# Transformer.net
KiCad netlist of a schematic drawn in Altium Designer
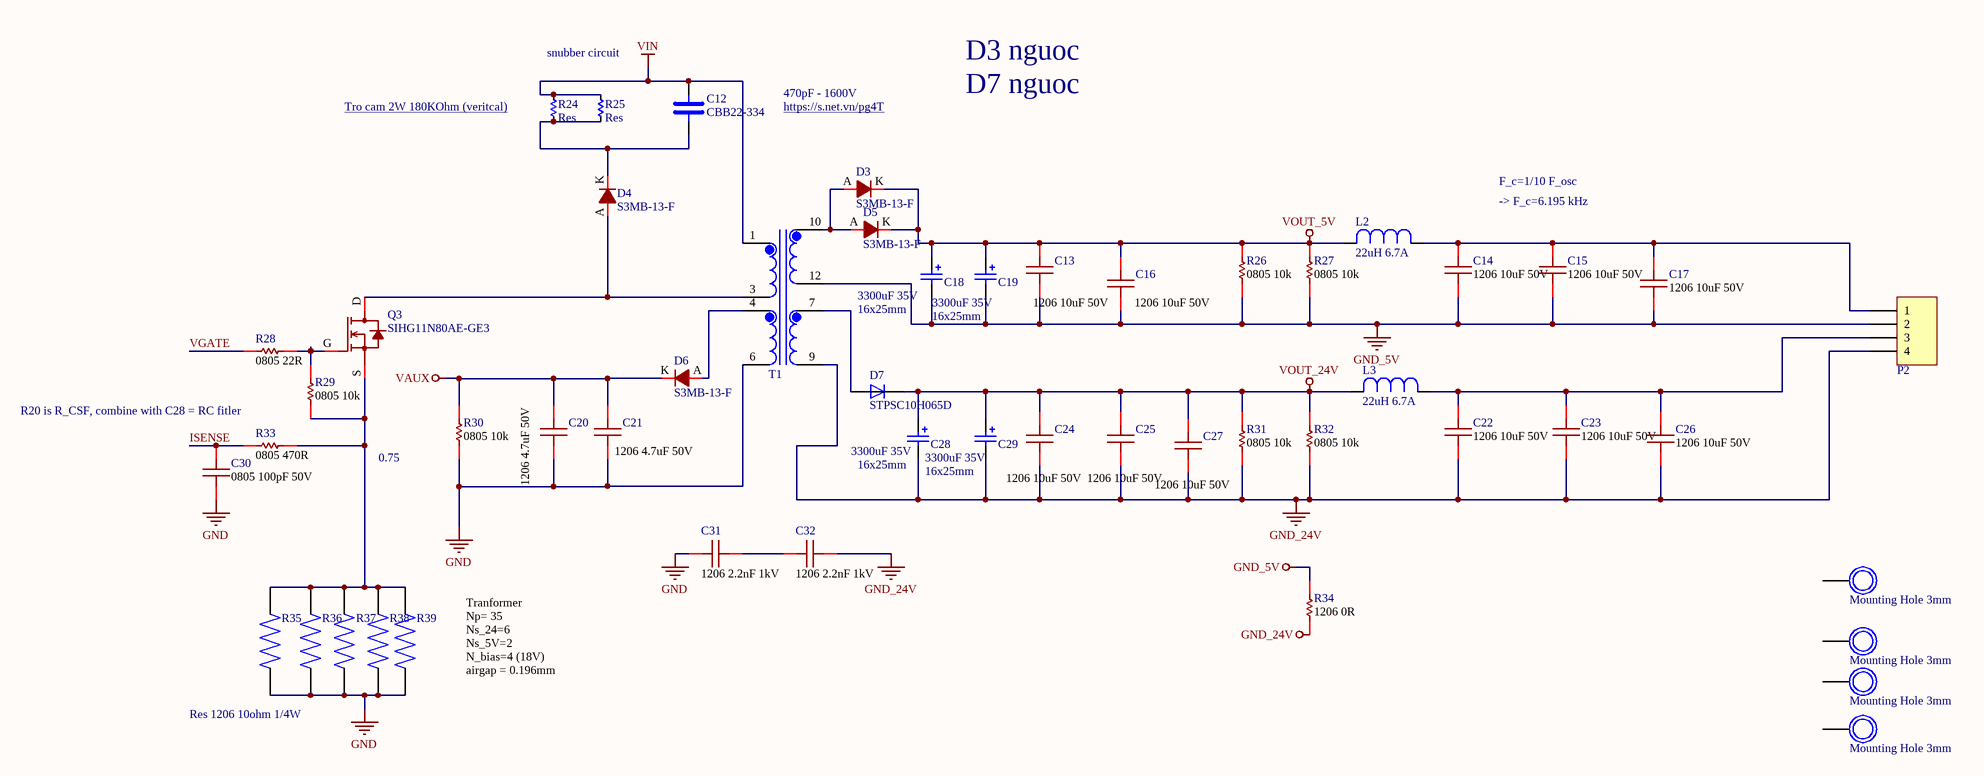
[diagram p0: Transformer.SchDoc]

(export (version "E")
  (design (tool "Eeschema 10.0.6"))
  (components
    (comp (ref "C12")
      (value "CBB22-334")
      (footprint "Cap 1600v")
      (description "CBB 630V 472J (4.7NF) 15mm")
      (libsource (lib "Mini_Chager_Lib_ALL") (part "CBB22-334"))
    )
    (comp (ref "C13")
      (value "1206 10uF 50V")
      (footprint "Cap 1206")
      (description "4.7 µF ±20% 50V Ceramic Capacitor X7R 1206 (3216 Metric)")
      (fields (field (name "TOLERANCE") "20%") (field (name "Comment") "C3216X7R1H475M160AC"))
      (libsource (lib "xEV_Flyback20W") (part "Cap 1206 4.7uF"))
    )
    (comp (ref "C14")
      (value "1206 10uF 50V")
      (footprint "Cap 1206")
      (description "4.7 µF ±20% 50V Ceramic Capacitor X7R 1206 (3216 Metric)")
      (fields (field (name "TOLERANCE") "20%") (field (name "Comment") "C3216X7R1H475M160AC"))
      (libsource (lib "xEV_Flyback20W") (part "Cap 1206 4.7uF"))
    )
    (comp (ref "C15")
      (value "1206 10uF 50V")
      (footprint "Cap 1206")
      (description "4.7 µF ±20% 50V Ceramic Capacitor X7R 1206 (3216 Metric)")
      (fields (field (name "TOLERANCE") "20%") (field (name "Comment") "C3216X7R1H475M160AC"))
      (libsource (lib "xEV_Flyback20W") (part "Cap 1206 4.7uF"))
    )
    (comp (ref "C16")
      (value "1206 10uF 50V")
      (footprint "Cap 1206")
      (description "4.7 µF ±20% 50V Ceramic Capacitor X7R 1206 (3216 Metric)")
      (fields (field (name "TOLERANCE") "20%") (field (name "Comment") "C3216X7R1H475M160AC"))
      (libsource (lib "xEV_Flyback20W") (part "Cap 1206 4.7uF"))
    )
    (comp (ref "C17")
      (value "1206 10uF 50V")
      (footprint "Cap 1206")
      (description "4.7 µF ±20% 50V Ceramic Capacitor X7R 1206 (3216 Metric)")
      (fields (field (name "TOLERANCE") "20%") (field (name "Comment") "C3216X7R1H475M160AC"))
      (libsource (lib "xEV_Flyback20W") (part "Cap 1206 4.7uF"))
    )
    (comp (ref "C18")
      (value "2700uF")
      (footprint "WCAP-ATG8_D16H25")
      (description "WCAP-ATG8 Aluminum Electrolytic Capacitor, Radial THT, D16xH25mm, 2700uF, 25V")
      (fields
        (field (name "MANUFACTURER") "Wurth Elektronik")
        (field (name "MANUFACTURER PART NUMBER") "860010480022")
      )
      (libsource (lib "Altium_WCAP-ATG8 (rev22a)") (part "860010480022"))
    )
    (comp (ref "C19")
      (value "2700uF")
      (footprint "WCAP-ATG8_D16H25")
      (description "WCAP-ATG8 Aluminum Electrolytic Capacitor, Radial THT, D16xH25mm, 2700uF, 25V")
      (fields
        (field (name "MANUFACTURER") "Wurth Elektronik")
        (field (name "MANUFACTURER PART NUMBER") "860010480022")
      )
      (libsource (lib "Altium_WCAP-ATG8 (rev22a)") (part "860010480022"))
    )
    (comp (ref "C20")
      (value "1206 4.7uF 50V")
      (footprint "Cap 1206")
      (description "4.7 µF ±20% 50V Ceramic Capacitor X7R 1206 (3216 Metric)")
      (fields (field (name "TOLERANCE") "20%") (field (name "Comment") "C3216X7R1H475M160AC"))
      (libsource (lib "xEV_Flyback20W") (part "Cap 1206 4.7uF"))
    )
    (comp (ref "C21")
      (value "1206 4.7uF 50V")
      (footprint "Cap 1206")
      (description "4.7 µF ±20% 50V Ceramic Capacitor X7R 1206 (3216 Metric)")
      (fields (field (name "TOLERANCE") "20%") (field (name "Comment") "C3216X7R1H475M160AC"))
      (libsource (lib "xEV_Flyback20W") (part "Cap 1206 4.7uF"))
    )
    (comp (ref "C22")
      (value "1206 10uF 50V")
      (footprint "Cap 1206")
      (description "4.7 µF ±20% 50V Ceramic Capacitor X7R 1206 (3216 Metric)")
      (fields (field (name "TOLERANCE") "20%") (field (name "Comment") "C3216X7R1H475M160AC"))
      (libsource (lib "xEV_Flyback20W") (part "Cap 1206 4.7uF"))
    )
    (comp (ref "C23")
      (value "1206 10uF 50V")
      (footprint "Cap 1206")
      (description "4.7 µF ±20% 50V Ceramic Capacitor X7R 1206 (3216 Metric)")
      (fields (field (name "TOLERANCE") "20%") (field (name "Comment") "C3216X7R1H475M160AC"))
      (libsource (lib "xEV_Flyback20W") (part "Cap 1206 4.7uF"))
    )
    (comp (ref "C24")
      (value "1206 10uF 50V")
      (footprint "Cap 1206")
      (description "4.7 µF ±20% 50V Ceramic Capacitor X7R 1206 (3216 Metric)")
      (fields (field (name "TOLERANCE") "20%") (field (name "Comment") "C3216X7R1H475M160AC"))
      (libsource (lib "xEV_Flyback20W") (part "Cap 1206 4.7uF"))
    )
    (comp (ref "C25")
      (value "1206 10uF 50V")
      (footprint "Cap 1206")
      (description "4.7 µF ±20% 50V Ceramic Capacitor X7R 1206 (3216 Metric)")
      (fields (field (name "TOLERANCE") "20%") (field (name "Comment") "C3216X7R1H475M160AC"))
      (libsource (lib "xEV_Flyback20W") (part "Cap 1206 4.7uF"))
    )
    (comp (ref "C26")
      (value "1206 10uF 50V")
      (footprint "Cap 1206")
      (description "4.7 µF ±20% 50V Ceramic Capacitor X7R 1206 (3216 Metric)")
      (fields (field (name "TOLERANCE") "20%") (field (name "Comment") "C3216X7R1H475M160AC"))
      (libsource (lib "xEV_Flyback20W") (part "Cap 1206 4.7uF"))
    )
    (comp (ref "C27")
      (value "1206 10uF 50V")
      (footprint "Cap 1206")
      (description "4.7 µF ±20% 50V Ceramic Capacitor X7R 1206 (3216 Metric)")
      (fields (field (name "TOLERANCE") "20%") (field (name "Comment") "C3216X7R1H475M160AC"))
      (libsource (lib "xEV_Flyback20W") (part "Cap 1206 4.7uF"))
    )
    (comp (ref "C28")
      (value "2700uF")
      (footprint "WCAP-ATG8_D16H25")
      (description "WCAP-ATG8 Aluminum Electrolytic Capacitor, Radial THT, D16xH25mm, 2700uF, 25V")
      (fields
        (field (name "MANUFACTURER") "Wurth Elektronik")
        (field (name "MANUFACTURER PART NUMBER") "860010480022")
      )
      (libsource (lib "Altium_WCAP-ATG8 (rev22a)") (part "860010480022"))
    )
    (comp (ref "C29")
      (value "2700uF")
      (footprint "WCAP-ATG8_D16H25")
      (description "WCAP-ATG8 Aluminum Electrolytic Capacitor, Radial THT, D16xH25mm, 2700uF, 25V")
      (fields
        (field (name "MANUFACTURER") "Wurth Elektronik")
        (field (name "MANUFACTURER PART NUMBER") "860010480022")
      )
      (libsource (lib "Altium_WCAP-ATG8 (rev22a)") (part "860010480022"))
    )
    (comp (ref "C30")
      (value "C0805C101J5RACTU")
      (footprint "CAP 0805")
      (description "CAP, CERM, 100 pF, 50 V, +/- 5%, X7R, 0805")
      (fields (field (name "PARAMETER 1") "0805 100pF 50V"))
      (libsource (lib "xEV_Flyback20W") (part "CAP 0805 100pF"))
    )
    (comp (ref "C31")
      (value "1206 2.2nF 1kV")
      (footprint "Cap 1206")
      (description "2200 pF ±10% 1000V (1kV) Ceramic Capacitor X7R 1206 (3216 Metric)")
      (fields (field (name "Comment") "CC1206KKX7RCBB222"))
      (libsource (lib "xEV_Flyback20W") (part "Cap 1206 2.2nF"))
    )
    (comp (ref "C32")
      (value "1206 2.2nF 1kV")
      (footprint "Cap 1206")
      (description "2200 pF ±10% 1000V (1kV) Ceramic Capacitor X7R 1206 (3216 Metric)")
      (fields (field (name "Comment") "CC1206KKX7RCBB222"))
      (libsource (lib "xEV_Flyback20W") (part "Cap 1206 2.2nF"))
    )
    (comp (ref "D3")
      (value "S3MB-13-F")
      (footprint "DIODE 1kV 3A")
      (description "DIODE GEN PURP 1KV 3A SMB")
      (fields
        (field (name "MANUFACTURER") "Diodes Inc.")
        (field (name "OCTOPART") "https://octopart.com/s3mb-13-f-diodes+inc.-333387")
      )
      (libsource (lib "xEV_Flyback20W") (part "DIODE 1000V 3A"))
    )
    (comp (ref "D4")
      (value "S3MB-13-F")
      (footprint "DIODE 1kV 3A")
      (description "DIODE GEN PURP 1KV 3A SMB")
      (fields
        (field (name "MANUFACTURER") "Diodes Inc.")
        (field (name "OCTOPART") "https://octopart.com/s3mb-13-f-diodes+inc.-333387")
      )
      (libsource (lib "xEV_Flyback20W") (part "DIODE 1000V 3A"))
    )
    (comp (ref "D5")
      (value "S3MB-13-F")
      (footprint "DIODE 1kV 3A")
      (description "DIODE GEN PURP 1KV 3A SMB")
      (fields
        (field (name "MANUFACTURER") "Diodes Inc.")
        (field (name "OCTOPART") "https://octopart.com/s3mb-13-f-diodes+inc.-333387")
      )
      (libsource (lib "xEV_Flyback20W") (part "DIODE 1000V 3A"))
    )
    (comp (ref "D6")
      (value "S3MB-13-F")
      (footprint "DIODE 1kV 3A")
      (description "DIODE GEN PURP 1KV 3A SMB")
      (fields
        (field (name "MANUFACTURER") "Diodes Inc.")
        (field (name "OCTOPART") "https://octopart.com/s3mb-13-f-diodes+inc.-333387")
      )
      (libsource (lib "xEV_Flyback20W") (part "DIODE 1000V 3A"))
    )
    (comp (ref "D7")
      (value "STPSC10H065D")
      (footprint "TO508P1016X470X2286-2")
      (libsource (lib "Mini_Chager_Lib_ALL") (part "STPSC10H065D"))
    )
    (comp (ref "H1")
      (value "Mounting Hole 3mm")
      (footprint "3mm with via")
      (libsource (lib "Altium_Mech") (part "Mounting Hole 3mm"))
    )
    (comp (ref "H2")
      (value "Mounting Hole 3mm")
      (footprint "3mm with via")
      (libsource (lib "Altium_Mech") (part "Mounting Hole 3mm"))
    )
    (comp (ref "H3")
      (value "Mounting Hole 3mm")
      (footprint "3mm with via")
      (libsource (lib "Altium_Mech") (part "Mounting Hole 3mm"))
    )
    (comp (ref "H4")
      (value "Mounting Hole 3mm")
      (footprint "3mm with via")
      (libsource (lib "Altium_Mech") (part "Mounting Hole 3mm"))
    )
    (comp (ref "L2")
      (value "22uH 6.7A")
      (footprint "IND_CDRH127/LDNP-470MC_SUM")
      (description "47 ÂµH Shielded - Inductor 3.25 A 78mOhm Max Nonstandard")
      (fields (field (name "MF") "Sumida America") (field (name "MP") "CDRH127/LDNP-470MC"))
      (libsource (lib "CDRH127_LDNP-470MC") (part "CDRH127/LDNP-470MC"))
    )
    (comp (ref "L3")
      (value "22uH 6.7A")
      (footprint "IND_CDRH127/LDNP-470MC_SUM")
      (description "47 ÂµH Shielded - Inductor 3.25 A 78mOhm Max Nonstandard")
      (fields (field (name "MF") "Sumida America") (field (name "MP") "CDRH127/LDNP-470MC"))
      (libsource (lib "CDRH127_LDNP-470MC") (part "CDRH127/LDNP-470MC"))
    )
    (comp (ref "P2")
      (value "Domino 4")
      (footprint "DOMINO 4 -5mm")
      (description "Domino 4-Pin")
      (fields (field (name "PUBLISHER") "Altium Limited"))
      (libsource (lib "PIF_Library") (part "Domino 4"))
    )
    (comp (ref "Q3")
      (value "SIHG11N80AE-GE3")
      (footprint "N-CH MOSFET 1k2V")
      (description "MOSFET N-CH 800V 8A TO247AC")
      (fields
        (field (name "MANUFACTURER_PART_NUMBER") "NVHL160N120SC1")
        (field (name "MOUSER PART NUMBER") "863-NVHL160N120SC1")
      )
      (libsource (lib "xEV_Flyback20W") (part "SIHG11N80AE-GE3"))
    )
    (comp (ref "R24")
      (value "Res")
      (footprint "RES-1WD")
      (fields
        (field (name "MANUFACTURER") "Generic Components")
        (field (name "PUBLISHER") "Altium Hobart Technology Centre")
      )
      (libsource (lib "TechMT.VN_Lib_Project v2") (part "Res"))
    )
    (comp (ref "R25")
      (value "Res")
      (footprint "RES-1WD")
      (fields
        (field (name "MANUFACTURER") "Generic Components")
        (field (name "PUBLISHER") "Altium Hobart Technology Centre")
      )
      (libsource (lib "TechMT.VN_Lib_Project v2") (part "Res"))
    )
    (comp (ref "R26")
      (value "0805 10k")
      (footprint "RES 0805")
      (description "10 kOhms ±1% 0.125W, 1/8W Chip Resistor 0805 (2012 Metric) Moisture Resistant Thick Film")
      (fields (field (name "Comment") "RC0805FR-1310KL"))
      (libsource (lib "xEV_Flyback20W") (part "RES_0805_10k"))
    )
    (comp (ref "R27")
      (value "0805 10k")
      (footprint "RES 0805")
      (description "10 kOhms ±1% 0.125W, 1/8W Chip Resistor 0805 (2012 Metric) Moisture Resistant Thick Film")
      (fields (field (name "Comment") "RC0805FR-1310KL"))
      (libsource (lib "xEV_Flyback20W") (part "RES_0805_10k"))
    )
    (comp (ref "R28")
      (value "0805 22R")
      (footprint "RES 0805")
      (fields (field (name "Comment") "RC0805FR-0722RP"))
      (libsource (lib "xEV_Flyback20W") (part "RES_0805_22R"))
    )
    (comp (ref "R29")
      (value "0805 10k")
      (footprint "RES 0805")
      (description "10 kOhms ±1% 0.125W, 1/8W Chip Resistor 0805 (2012 Metric) Moisture Resistant Thick Film")
      (fields (field (name "Comment") "RC0805FR-1310KL"))
      (libsource (lib "xEV_Flyback20W") (part "RES_0805_10k"))
    )
    (comp (ref "R30")
      (value "0805 10k")
      (footprint "RES 0805")
      (description "10 kOhms ±1% 0.125W, 1/8W Chip Resistor 0805 (2012 Metric) Moisture Resistant Thick Film")
      (fields (field (name "Comment") "RC0805FR-1310KL"))
      (libsource (lib "xEV_Flyback20W") (part "RES_0805_10k"))
    )
    (comp (ref "R31")
      (value "0805 10k")
      (footprint "RES 0805")
      (description "10 kOhms ±1% 0.125W, 1/8W Chip Resistor 0805 (2012 Metric) Moisture Resistant Thick Film")
      (fields (field (name "Comment") "RC0805FR-1310KL"))
      (libsource (lib "xEV_Flyback20W") (part "RES_0805_10k"))
    )
    (comp (ref "R32")
      (value "0805 10k")
      (footprint "RES 0805")
      (description "10 kOhms ±1% 0.125W, 1/8W Chip Resistor 0805 (2012 Metric) Moisture Resistant Thick Film")
      (fields (field (name "Comment") "RC0805FR-1310KL"))
      (libsource (lib "xEV_Flyback20W") (part "RES_0805_10k"))
    )
    (comp (ref "R33")
      (value "0805 470R")
      (footprint "RES 0805")
      (description "470 Ohms ±1% 0.125W, 1/8W Chip Resistor 0805 (2012 Metric) Moisture Resistant Thick Film")
      (fields (field (name "Comment") "RC0805FR-07470RP"))
      (libsource (lib "xEV_Flyback20W") (part "RES_0805_470"))
    )
    (comp (ref "R34")
      (value "1206 0R")
      (footprint "xEV_Flyback20W:RES 1206")
      (description "0 Ohms ±5% 1W, Moisture Resistant Thick Film")
      (fields
        (field (name "MANUFACTURER_PART_NUMBER") "CR1206-F/-2R00ELF")
        (field (name "MOUSER PART NUMBER") "652-CR1206-F/2R00ELF")
      )
      (libsource (lib "xEV_Flyback20W") (part "RES_1206_0R"))
    )
    (comp (ref "R35")
      (value "RC1206JR-0713RL")
      (footprint "RESC3116X65N")
      (description "13 Ohms Â±5% 0.25W, 1/4W Chip Resistor 1206 (3216 Metric) Moisture Resistant Thick Film")
      (fields (field (name "MF") "Yageo"))
      (libsource (lib "RC1206JR-0713RL (1)") (part "RC1206JR-0713RL"))
    )
    (comp (ref "R36")
      (value "RC1206JR-0713RL")
      (footprint "RESC3116X65N")
      (description "13 Ohms Â±5% 0.25W, 1/4W Chip Resistor 1206 (3216 Metric) Moisture Resistant Thick Film")
      (fields (field (name "MF") "Yageo"))
      (libsource (lib "RC1206JR-0713RL (1)") (part "RC1206JR-0713RL"))
    )
    (comp (ref "R37")
      (value "RC1206JR-0713RL")
      (footprint "RESC3116X65N")
      (description "13 Ohms Â±5% 0.25W, 1/4W Chip Resistor 1206 (3216 Metric) Moisture Resistant Thick Film")
      (fields (field (name "MF") "Yageo"))
      (libsource (lib "RC1206JR-0713RL (1)") (part "RC1206JR-0713RL"))
    )
    (comp (ref "R38")
      (value "RC1206JR-0713RL")
      (footprint "RESC3116X65N")
      (description "13 Ohms Â±5% 0.25W, 1/4W Chip Resistor 1206 (3216 Metric) Moisture Resistant Thick Film")
      (fields (field (name "MF") "Yageo"))
      (libsource (lib "RC1206JR-0713RL (1)") (part "RC1206JR-0713RL"))
    )
    (comp (ref "R39")
      (value "RC1206JR-0713RL")
      (footprint "RESC3116X65N")
      (description "13 Ohms Â±5% 0.25W, 1/4W Chip Resistor 1206 (3216 Metric) Moisture Resistant Thick Film")
      (fields (field (name "MF") "Yageo"))
      (libsource (lib "RC1206JR-0713RL (1)") (part "RC1206JR-0713RL"))
    )
    (comp (ref "T1")
      (value "PQ35")
      (footprint "CPV-PQ3535-1S-12P-Z_FXC")
      (description "Main Tranformer with 2 output line")
      (libsource (lib "Mini_Chager_Lib_ALL") (part "PQ35"))
    )
  )
  (nets
    (net (code "1") (name "/ISENSE") (class "Default")
      (node (ref "C30") (pin "1") (pinfunction "1_1") (pintype "passive"))
      (node (ref "R33") (pin "1") (pinfunction "1_1") (pintype "passive"))
    )
    (net (code "2") (name "/VGATE") (class "Default")
      (node (ref "R28") (pin "1") (pinfunction "1_1") (pintype "passive"))
    )
    (net (code "3") (name "GND") (class "Default")
      (node (ref "C20") (pin "2") (pinfunction "2_2") (pintype "passive"))
      (node (ref "C21") (pin "2") (pinfunction "2_2") (pintype "passive"))
      (node (ref "C30") (pin "2") (pinfunction "2_2") (pintype "passive"))
      (node (ref "C31") (pin "1") (pinfunction "1_1") (pintype "passive"))
      (node (ref "R30") (pin "1") (pinfunction "1_1") (pintype "passive"))
      (node (ref "R35") (pin "1") (pinfunction "1_1") (pintype "passive"))
      (node (ref "R36") (pin "1") (pinfunction "1_1") (pintype "passive"))
      (node (ref "R37") (pin "1") (pinfunction "1_1") (pintype "passive"))
      (node (ref "R38") (pin "1") (pinfunction "1_1") (pintype "passive"))
      (node (ref "R39") (pin "1") (pinfunction "1_1") (pintype "passive"))
      (node (ref "T1") (pin "6") (pinfunction "2_6") (pintype "passive"))
    )
    (net (code "4") (name "GND_5V") (class "Default")
      (node (ref "C13") (pin "2") (pinfunction "2_2") (pintype "passive"))
      (node (ref "C14") (pin "2") (pinfunction "2_2") (pintype "passive"))
      (node (ref "C15") (pin "2") (pinfunction "2_2") (pintype "passive"))
      (node (ref "C16") (pin "2") (pinfunction "2_2") (pintype "passive"))
      (node (ref "C17") (pin "2") (pinfunction "2_2") (pintype "passive"))
      (node (ref "C18") (pin "2") (pinfunction "N_2") (pintype "passive"))
      (node (ref "C19") (pin "2") (pinfunction "N_2") (pintype "passive"))
      (node (ref "P2") (pin "2") (pinfunction "2_2") (pintype "passive"))
      (node (ref "R26") (pin "1") (pinfunction "1_1") (pintype "passive"))
      (node (ref "R27") (pin "1") (pinfunction "1_1") (pintype "passive"))
      (node (ref "R34") (pin "2") (pinfunction "2_2") (pintype "passive"))
      (node (ref "T1") (pin "12") (pinfunction "4_12") (pintype "passive"))
    )
    (net (code "5") (name "GND_24V") (class "Default")
      (node (ref "C22") (pin "2") (pinfunction "2_2") (pintype "passive"))
      (node (ref "C23") (pin "2") (pinfunction "2_2") (pintype "passive"))
      (node (ref "C24") (pin "2") (pinfunction "2_2") (pintype "passive"))
      (node (ref "C25") (pin "2") (pinfunction "2_2") (pintype "passive"))
      (node (ref "C26") (pin "2") (pinfunction "2_2") (pintype "passive"))
      (node (ref "C27") (pin "2") (pinfunction "2_2") (pintype "passive"))
      (node (ref "C28") (pin "2") (pinfunction "N_2") (pintype "passive"))
      (node (ref "C29") (pin "2") (pinfunction "N_2") (pintype "passive"))
      (node (ref "C32") (pin "2") (pinfunction "2_2") (pintype "passive"))
      (node (ref "P2") (pin "4") (pinfunction "4_4") (pintype "passive"))
      (node (ref "R31") (pin "1") (pinfunction "1_1") (pintype "passive"))
      (node (ref "R32") (pin "1") (pinfunction "1_1") (pintype "passive"))
      (node (ref "R34") (pin "1") (pinfunction "1_1") (pintype "passive"))
      (node (ref "T1") (pin "9") (pinfunction "6_9") (pintype "passive"))
    )
    (net (code "6") (name "Net-(C14-Pad1)") (class "Default")
      (node (ref "C14") (pin "1") (pinfunction "1_1") (pintype "passive"))
      (node (ref "C15") (pin "1") (pinfunction "1_1") (pintype "passive"))
      (node (ref "C17") (pin "1") (pinfunction "1_1") (pintype "passive"))
      (node (ref "L2") (pin "1") (pinfunction "1_1") (pintype "passive"))
      (node (ref "P2") (pin "1") (pinfunction "1_1") (pintype "passive"))
    )
    (net (code "7") (name "Net-(C22-Pad1)") (class "Default")
      (node (ref "C22") (pin "1") (pinfunction "1_1") (pintype "passive"))
      (node (ref "C23") (pin "1") (pinfunction "1_1") (pintype "passive"))
      (node (ref "C26") (pin "1") (pinfunction "1_1") (pintype "passive"))
      (node (ref "L3") (pin "1") (pinfunction "1_1") (pintype "passive"))
      (node (ref "P2") (pin "3") (pinfunction "3_3") (pintype "passive"))
    )
    (net (code "8") (name "Net-(C31-Pad2)") (class "Default")
      (node (ref "C31") (pin "2") (pinfunction "2_2") (pintype "passive"))
      (node (ref "C32") (pin "1") (pinfunction "1_1") (pintype "passive"))
    )
    (net (code "9") (name "Net-(D3-1)") (class "Default")
      (node (ref "D3") (pin "A") (pinfunction "1_A") (pintype "passive"))
      (node (ref "D5") (pin "A") (pinfunction "1_A") (pintype "passive"))
      (node (ref "T1") (pin "10") (pinfunction "3_10") (pintype "passive"))
    )
    (net (code "10") (name "Net-(D4-1)") (class "Default")
      (node (ref "D4") (pin "A") (pinfunction "1_A") (pintype "passive"))
      (node (ref "Q3") (pin "D") (pinfunction "3_D") (pintype "passive"))
      (node (ref "T1") (pin "3") (pinfunction "2_3") (pintype "passive"))
    )
    (net (code "11") (name "Net-(D4-2)") (class "Default")
      (node (ref "C12") (pin "1") (pinfunction "1_1") (pintype "passive"))
      (node (ref "D4") (pin "K") (pinfunction "2_K") (pintype "passive"))
      (node (ref "R24") (pin "2") (pinfunction "2_2") (pintype "passive"))
      (node (ref "R25") (pin "2") (pinfunction "2_2") (pintype "passive"))
    )
    (net (code "12") (name "Net-(D6-1)") (class "Default")
      (node (ref "D6") (pin "A") (pinfunction "1_A") (pintype "passive"))
      (node (ref "T1") (pin "4") (pinfunction "1_4") (pintype "passive"))
    )
    (net (code "13") (name "Net-(D7-A)") (class "Default")
      (node (ref "D7") (pin "2") (pinfunction "A_2") (pintype "passive"))
      (node (ref "T1") (pin "7") (pinfunction "5_7") (pintype "passive"))
    )
    (net (code "14") (name "Net-(Q3-1)") (class "Default")
      (node (ref "Q3") (pin "G") (pinfunction "1_G") (pintype "passive"))
      (node (ref "R28") (pin "2") (pinfunction "2_2") (pintype "passive"))
      (node (ref "R29") (pin "2") (pinfunction "2_2") (pintype "passive"))
    )
    (net (code "15") (name "Net-(Q3-2)") (class "Default")
      (node (ref "Q3") (pin "S") (pinfunction "2_S") (pintype "passive"))
      (node (ref "R29") (pin "1") (pinfunction "1_1") (pintype "passive"))
      (node (ref "R33") (pin "2") (pinfunction "2_2") (pintype "passive"))
      (node (ref "R35") (pin "2") (pinfunction "2_2") (pintype "passive"))
      (node (ref "R36") (pin "2") (pinfunction "2_2") (pintype "passive"))
      (node (ref "R37") (pin "2") (pinfunction "2_2") (pintype "passive"))
      (node (ref "R38") (pin "2") (pinfunction "2_2") (pintype "passive"))
      (node (ref "R39") (pin "2") (pinfunction "2_2") (pintype "passive"))
    )
    (net (code "16") (name "VAUX") (class "Default")
      (node (ref "C20") (pin "1") (pinfunction "1_1") (pintype "passive"))
      (node (ref "C21") (pin "1") (pinfunction "1_1") (pintype "passive"))
      (node (ref "D6") (pin "K") (pinfunction "2_K") (pintype "passive"))
      (node (ref "R30") (pin "2") (pinfunction "2_2") (pintype "passive"))
    )
    (net (code "17") (name "VIN") (class "Default")
      (node (ref "C12") (pin "2") (pinfunction "2_2") (pintype "passive"))
      (node (ref "R24") (pin "1") (pinfunction "1_1") (pintype "passive"))
      (node (ref "R25") (pin "1") (pinfunction "1_1") (pintype "passive"))
      (node (ref "T1") (pin "1") (pinfunction "1_1") (pintype "passive"))
    )
    (net (code "18") (name "VOUT_5V") (class "Default")
      (node (ref "C13") (pin "1") (pinfunction "1_1") (pintype "passive"))
      (node (ref "C16") (pin "1") (pinfunction "1_1") (pintype "passive"))
      (node (ref "C18") (pin "1") (pinfunction "P_1") (pintype "passive"))
      (node (ref "C19") (pin "1") (pinfunction "P_1") (pintype "passive"))
      (node (ref "D3") (pin "K") (pinfunction "2_K") (pintype "passive"))
      (node (ref "D5") (pin "K") (pinfunction "2_K") (pintype "passive"))
      (node (ref "L2") (pin "2") (pinfunction "2_2") (pintype "passive"))
      (node (ref "R26") (pin "2") (pinfunction "2_2") (pintype "passive"))
      (node (ref "R27") (pin "2") (pinfunction "2_2") (pintype "passive"))
    )
    (net (code "19") (name "VOUT_24V") (class "Default")
      (node (ref "C24") (pin "1") (pinfunction "1_1") (pintype "passive"))
      (node (ref "C25") (pin "1") (pinfunction "1_1") (pintype "passive"))
      (node (ref "C27") (pin "1") (pinfunction "1_1") (pintype "passive"))
      (node (ref "C28") (pin "1") (pinfunction "P_1") (pintype "passive"))
      (node (ref "C29") (pin "1") (pinfunction "P_1") (pintype "passive"))
      (node (ref "D7") (pin "1") (pinfunction "C_1") (pintype "passive"))
      (node (ref "L3") (pin "2") (pinfunction "2_2") (pintype "passive"))
      (node (ref "R31") (pin "2") (pinfunction "2_2") (pintype "passive"))
      (node (ref "R32") (pin "2") (pinfunction "2_2") (pintype "passive"))
    )
    (net (code "20") (name "unconnected-(H1-Pad0)") (class "Default")
      (node (ref "H1") (pin "0") (pinfunction "0_0") (pintype "passive"))
    )
    (net (code "21") (name "unconnected-(H2-Pad0)") (class "Default")
      (node (ref "H2") (pin "0") (pinfunction "0_0") (pintype "passive"))
    )
    (net (code "22") (name "unconnected-(H3-Pad0)") (class "Default")
      (node (ref "H3") (pin "0") (pinfunction "0_0") (pintype "passive"))
    )
    (net (code "23") (name "unconnected-(H4-Pad0)") (class "Default")
      (node (ref "H4") (pin "0") (pinfunction "0_0") (pintype "passive"))
    )
  )
)
